# connector.net
KiCad netlist of a schematic drawn in Altium Designer
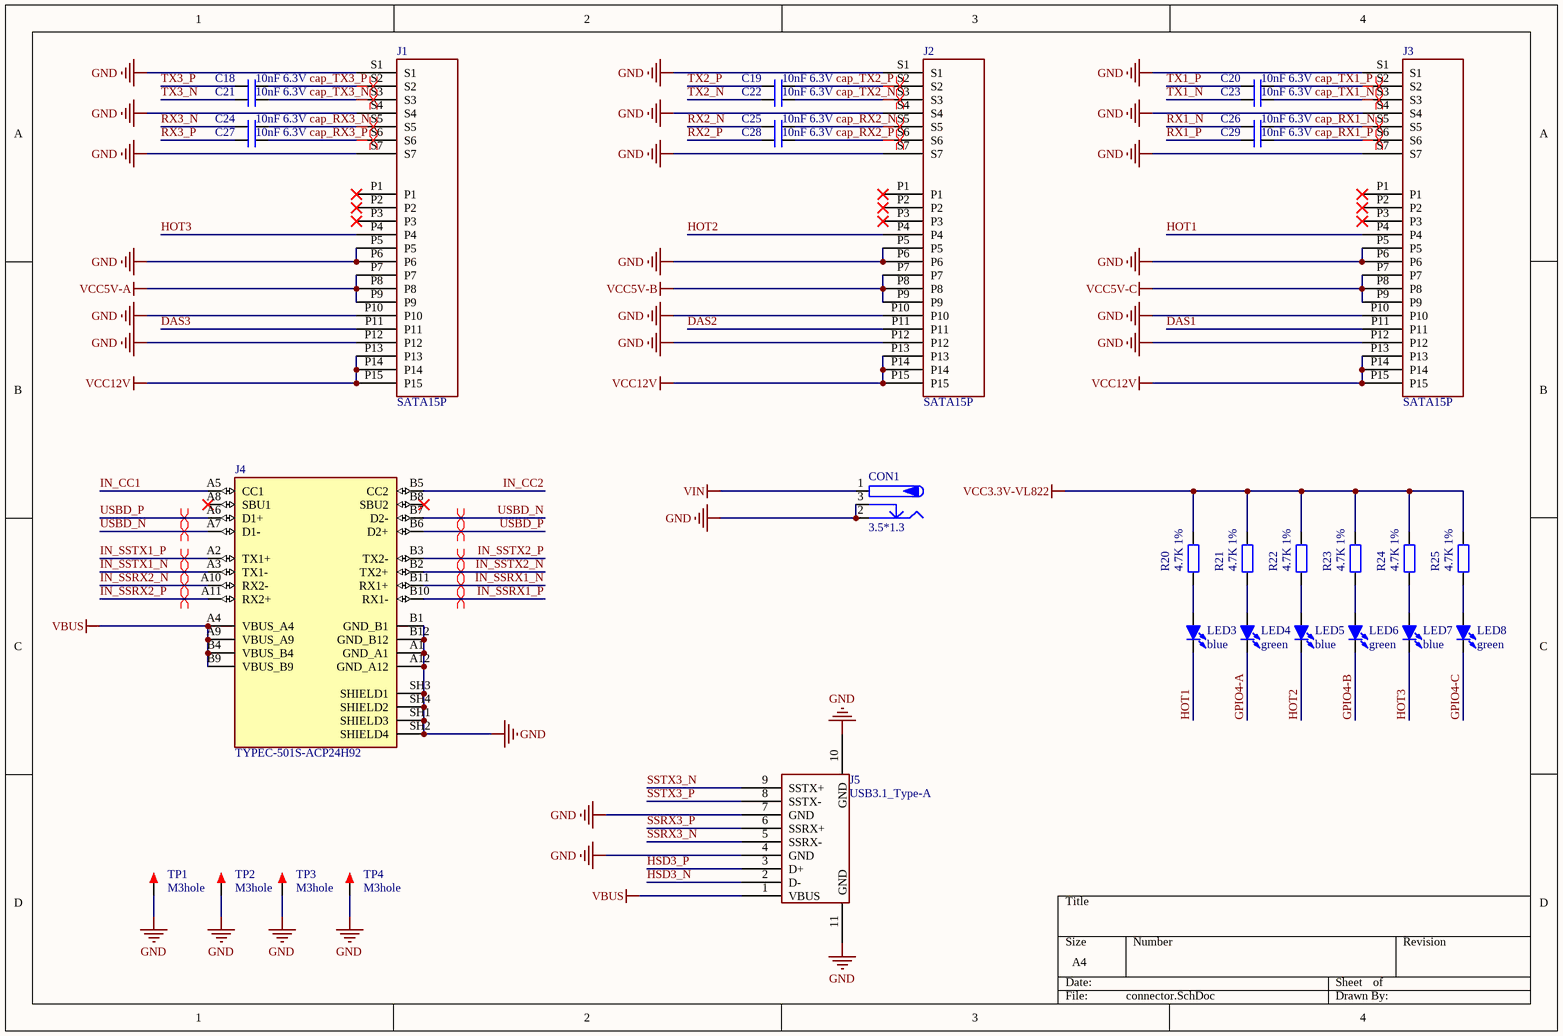
[diagram p0: connector.SchDoc]

(export (version "E")
  (design (tool "Eeschema 10.0.6"))
  (components
    (comp (ref "C18")
      (value "10nF 6.3V")
      (footprint "C0402_L")
      (description "无极性贴片电容")
      (fields (field (name "版权归属") "源创客"))
      (libsource (lib "Capacitor") (part "C"))
    )
    (comp (ref "C19")
      (value "10nF 6.3V")
      (footprint "C0402_L")
      (description "无极性贴片电容")
      (fields (field (name "版权归属") "源创客"))
      (libsource (lib "Capacitor") (part "C"))
    )
    (comp (ref "C20")
      (value "10nF 6.3V")
      (footprint "C0402_L")
      (description "无极性贴片电容")
      (fields (field (name "版权归属") "源创客"))
      (libsource (lib "Capacitor") (part "C"))
    )
    (comp (ref "C21")
      (value "10nF 6.3V")
      (footprint "C0402_L")
      (description "无极性贴片电容")
      (fields (field (name "版权归属") "源创客"))
      (libsource (lib "Capacitor") (part "C"))
    )
    (comp (ref "C22")
      (value "10nF 6.3V")
      (footprint "C0402_L")
      (description "无极性贴片电容")
      (fields (field (name "版权归属") "源创客"))
      (libsource (lib "Capacitor") (part "C"))
    )
    (comp (ref "C23")
      (value "10nF 6.3V")
      (footprint "C0402_L")
      (description "无极性贴片电容")
      (fields (field (name "版权归属") "源创客"))
      (libsource (lib "Capacitor") (part "C"))
    )
    (comp (ref "C24")
      (value "10nF 6.3V")
      (footprint "C0402_L")
      (description "无极性贴片电容")
      (fields (field (name "版权归属") "源创客"))
      (libsource (lib "Capacitor") (part "C"))
    )
    (comp (ref "C25")
      (value "10nF 6.3V")
      (footprint "C0402_L")
      (description "无极性贴片电容")
      (fields (field (name "版权归属") "源创客"))
      (libsource (lib "Capacitor") (part "C"))
    )
    (comp (ref "C26")
      (value "10nF 6.3V")
      (footprint "C0402_L")
      (description "无极性贴片电容")
      (fields (field (name "版权归属") "源创客"))
      (libsource (lib "Capacitor") (part "C"))
    )
    (comp (ref "C27")
      (value "10nF 6.3V")
      (footprint "C0402_L")
      (description "无极性贴片电容")
      (fields (field (name "版权归属") "源创客"))
      (libsource (lib "Capacitor") (part "C"))
    )
    (comp (ref "C28")
      (value "10nF 6.3V")
      (footprint "C0402_L")
      (description "无极性贴片电容")
      (fields (field (name "版权归属") "源创客"))
      (libsource (lib "Capacitor") (part "C"))
    )
    (comp (ref "C29")
      (value "10nF 6.3V")
      (footprint "C0402_L")
      (description "无极性贴片电容")
      (fields (field (name "版权归属") "源创客"))
      (libsource (lib "Capacitor") (part "C"))
    )
    (comp (ref "CON1")
      (value "3.5*1.3")
      (footprint "DC-012")
      (description "低压电源接口")
      (fields (field (name "版权归属") "源创客"))
      (libsource (lib "Connector-PWR") (part "P-DC"))
    )
    (comp (ref "J1")
      (value "SATA15P")
      (footprint "SATA 15P 贴片")
      (libsource (lib "Connector-SATA&SAS") (part "SATA15P"))
    )
    (comp (ref "J2")
      (value "SATA15P")
      (footprint "SATA 15P 贴片")
      (libsource (lib "Connector-SATA&SAS") (part "SATA15P"))
    )
    (comp (ref "J3")
      (value "SATA15P")
      (footprint "SATA 15P 贴片")
      (libsource (lib "Connector-SATA&SAS") (part "SATA15P"))
    )
    (comp (ref "J4")
      (value "TYPEC-501S-ACP24H92")
      (footprint "TypeC 24p 直立")
      (fields (field (name "MF") "Molex") (field (name "MP") "1054500101"))
      (libsource (lib "Connector-USB") (part "Typec 24p"))
    )
    (comp (ref "J5")
      (value "USB3.1_Type-A")
      (footprint "USB3.1_Type-A 立式直插")
      (description "USB接口")
      (libsource (lib "Connector-USB") (part "USB3.1_Type-A"))
    )
    (comp (ref "LED3")
      (value "blue")
      (footprint "LED 0805B")
      (description "插件LED")
      (fields (field (name "版权归属") "源创客"))
      (libsource (lib "LED") (part "LED-3MM"))
    )
    (comp (ref "LED4")
      (value "green")
      (footprint "LED 0805G")
      (description "插件LED")
      (fields (field (name "版权归属") "源创客"))
      (libsource (lib "LED") (part "LED-3MM"))
    )
    (comp (ref "LED5")
      (value "blue")
      (footprint "LED 0805B")
      (description "插件LED")
      (fields (field (name "版权归属") "源创客"))
      (libsource (lib "LED") (part "LED-3MM"))
    )
    (comp (ref "LED6")
      (value "green")
      (footprint "LED 0805G")
      (description "插件LED")
      (fields (field (name "版权归属") "源创客"))
      (libsource (lib "LED") (part "LED-3MM"))
    )
    (comp (ref "LED7")
      (value "blue")
      (footprint "LED 0805B")
      (description "插件LED")
      (fields (field (name "版权归属") "源创客"))
      (libsource (lib "LED") (part "LED-3MM"))
    )
    (comp (ref "LED8")
      (value "green")
      (footprint "LED 0805G")
      (description "插件LED")
      (fields (field (name "版权归属") "源创客"))
      (libsource (lib "LED") (part "LED-3MM"))
    )
    (comp (ref "R20")
      (value "4.7K 1%")
      (footprint "R0402_L")
      (description "贴片电阻")
      (fields (field (name "版权归属") "源创客"))
      (libsource (lib "Resistor") (part "R"))
    )
    (comp (ref "R21")
      (value "4.7K 1%")
      (footprint "R0402_L")
      (description "贴片电阻")
      (fields (field (name "版权归属") "源创客"))
      (libsource (lib "Resistor") (part "R"))
    )
    (comp (ref "R22")
      (value "4.7K 1%")
      (footprint "R0402_L")
      (description "贴片电阻")
      (fields (field (name "版权归属") "源创客"))
      (libsource (lib "Resistor") (part "R"))
    )
    (comp (ref "R23")
      (value "4.7K 1%")
      (footprint "R0402_L")
      (description "贴片电阻")
      (fields (field (name "版权归属") "源创客"))
      (libsource (lib "Resistor") (part "R"))
    )
    (comp (ref "R24")
      (value "4.7K 1%")
      (footprint "R0402_L")
      (description "贴片电阻")
      (fields (field (name "版权归属") "源创客"))
      (libsource (lib "Resistor") (part "R"))
    )
    (comp (ref "R25")
      (value "4.7K 1%")
      (footprint "R0402_L")
      (description "贴片电阻")
      (fields (field (name "版权归属") "源创客"))
      (libsource (lib "Resistor") (part "R"))
    )
    (comp (ref "TP1")
      (value "M3hole")
      (footprint "m3内嵌螺母贴片")
      (description "测试点")
      (fields (field (name "版权归属") "源创客"))
      (libsource (lib "Hole") (part "TEST"))
    )
    (comp (ref "TP2")
      (value "M3hole")
      (footprint "m3内嵌螺母贴片")
      (description "测试点")
      (fields (field (name "版权归属") "源创客"))
      (libsource (lib "Hole") (part "TEST"))
    )
    (comp (ref "TP3")
      (value "M3hole")
      (footprint "m3内嵌螺母贴片")
      (description "测试点")
      (fields (field (name "版权归属") "源创客"))
      (libsource (lib "Hole") (part "TEST"))
    )
    (comp (ref "TP4")
      (value "M3hole")
      (footprint "m3内嵌螺母贴片")
      (description "测试点")
      (fields (field (name "版权归属") "源创客"))
      (libsource (lib "Hole") (part "TEST"))
    )
  )
  (nets
    (net (code "1") (name "/DAS1") (class "Default")
      (node (ref "J3") (pin "P11") (pinfunction "P11_P11") (pintype "passive"))
    )
    (net (code "2") (name "/DAS2") (class "Default")
      (node (ref "J2") (pin "P11") (pinfunction "P11_P11") (pintype "passive"))
    )
    (net (code "3") (name "/DAS3") (class "Default")
      (node (ref "J1") (pin "P11") (pinfunction "P11_P11") (pintype "passive"))
    )
    (net (code "4") (name "/GPIO4-A") (class "Default")
      (node (ref "LED4") (pin "2") (pinfunction "K_2") (pintype "passive"))
    )
    (net (code "5") (name "/GPIO4-B") (class "Default")
      (node (ref "LED6") (pin "2") (pinfunction "K_2") (pintype "passive"))
    )
    (net (code "6") (name "/GPIO4-C") (class "Default")
      (node (ref "LED8") (pin "2") (pinfunction "K_2") (pintype "passive"))
    )
    (net (code "7") (name "/HOT1") (class "Default")
      (node (ref "J3") (pin "P4") (pinfunction "P4_P4") (pintype "passive"))
      (node (ref "LED3") (pin "2") (pinfunction "K_2") (pintype "passive"))
    )
    (net (code "8") (name "/HOT2") (class "Default")
      (node (ref "J2") (pin "P4") (pinfunction "P4_P4") (pintype "passive"))
      (node (ref "LED5") (pin "2") (pinfunction "K_2") (pintype "passive"))
    )
    (net (code "9") (name "/HOT3") (class "Default")
      (node (ref "J1") (pin "P4") (pinfunction "P4_P4") (pintype "passive"))
      (node (ref "LED7") (pin "2") (pinfunction "K_2") (pintype "passive"))
    )
    (net (code "10") (name "/HSD3_N") (class "Default")
      (node (ref "J5") (pin "2") (pinfunction "D-_2") (pintype "passive"))
    )
    (net (code "11") (name "/HSD3_P") (class "Default")
      (node (ref "J5") (pin "3") (pinfunction "D+_3") (pintype "passive"))
    )
    (net (code "12") (name "/IN_CC1") (class "Default")
      (node (ref "J4") (pin "A5") (pinfunction "CC1_A5") (pintype "bidirectional"))
    )
    (net (code "13") (name "/IN_CC2") (class "Default")
      (node (ref "J4") (pin "B5") (pinfunction "CC2_B5") (pintype "bidirectional"))
    )
    (net (code "14") (name "/IN_SSRX1_N") (class "Default")
      (node (ref "J4") (pin "B11") (pinfunction "RX1+_B11") (pintype "bidirectional"))
    )
    (net (code "15") (name "/IN_SSRX1_P") (class "Default")
      (node (ref "J4") (pin "B10") (pinfunction "RX1-_B10") (pintype "bidirectional"))
    )
    (net (code "16") (name "/IN_SSRX2_N") (class "Default")
      (node (ref "J4") (pin "A10") (pinfunction "RX2-_A10") (pintype "bidirectional"))
    )
    (net (code "17") (name "/IN_SSRX2_P") (class "Default")
      (node (ref "J4") (pin "A11") (pinfunction "RX2+_A11") (pintype "bidirectional"))
    )
    (net (code "18") (name "/IN_SSTX1_N") (class "Default")
      (node (ref "J4") (pin "A3") (pinfunction "TX1-_A3") (pintype "bidirectional"))
    )
    (net (code "19") (name "/IN_SSTX1_P") (class "Default")
      (node (ref "J4") (pin "A2") (pinfunction "TX1+_A2") (pintype "bidirectional"))
    )
    (net (code "20") (name "/IN_SSTX2_N") (class "Default")
      (node (ref "J4") (pin "B2") (pinfunction "TX2+_B2") (pintype "bidirectional"))
    )
    (net (code "21") (name "/IN_SSTX2_P") (class "Default")
      (node (ref "J4") (pin "B3") (pinfunction "TX2-_B3") (pintype "bidirectional"))
    )
    (net (code "22") (name "/RX1_N") (class "Default")
      (node (ref "C26") (pin "2") (pinfunction "2_2") (pintype "passive"))
    )
    (net (code "23") (name "/RX1_P") (class "Default")
      (node (ref "C29") (pin "2") (pinfunction "2_2") (pintype "passive"))
    )
    (net (code "24") (name "/RX2_N") (class "Default")
      (node (ref "C25") (pin "2") (pinfunction "2_2") (pintype "passive"))
    )
    (net (code "25") (name "/RX2_P") (class "Default")
      (node (ref "C28") (pin "2") (pinfunction "2_2") (pintype "passive"))
    )
    (net (code "26") (name "/RX3_N") (class "Default")
      (node (ref "C24") (pin "2") (pinfunction "2_2") (pintype "passive"))
    )
    (net (code "27") (name "/RX3_P") (class "Default")
      (node (ref "C27") (pin "2") (pinfunction "2_2") (pintype "passive"))
    )
    (net (code "28") (name "/SSRX3_N") (class "Default")
      (node (ref "J5") (pin "5") (pinfunction "SSRX-_5") (pintype "passive"))
    )
    (net (code "29") (name "/SSRX3_P") (class "Default")
      (node (ref "J5") (pin "6") (pinfunction "SSRX+_6") (pintype "passive"))
    )
    (net (code "30") (name "/SSTX3_N") (class "Default")
      (node (ref "J5") (pin "9") (pinfunction "SSTX+_9") (pintype "passive"))
    )
    (net (code "31") (name "/SSTX3_P") (class "Default")
      (node (ref "J5") (pin "8") (pinfunction "SSTX-_8") (pintype "passive"))
    )
    (net (code "32") (name "/TX1_N") (class "Default")
      (node (ref "C23") (pin "2") (pinfunction "2_2") (pintype "passive"))
    )
    (net (code "33") (name "/TX1_P") (class "Default")
      (node (ref "C20") (pin "2") (pinfunction "2_2") (pintype "passive"))
    )
    (net (code "34") (name "/TX2_N") (class "Default")
      (node (ref "C22") (pin "2") (pinfunction "2_2") (pintype "passive"))
    )
    (net (code "35") (name "/TX2_P") (class "Default")
      (node (ref "C19") (pin "2") (pinfunction "2_2") (pintype "passive"))
    )
    (net (code "36") (name "/TX3_N") (class "Default")
      (node (ref "C21") (pin "2") (pinfunction "2_2") (pintype "passive"))
    )
    (net (code "37") (name "/TX3_P") (class "Default")
      (node (ref "C18") (pin "2") (pinfunction "2_2") (pintype "passive"))
    )
    (net (code "38") (name "/USBD_N") (class "Default")
      (node (ref "J4") (pin "A7") (pinfunction "D1-_A7") (pintype "bidirectional"))
      (node (ref "J4") (pin "B7") (pinfunction "D2-_B7") (pintype "bidirectional"))
    )
    (net (code "39") (name "/USBD_P") (class "Default")
      (node (ref "J4") (pin "A6") (pinfunction "D1+_A6") (pintype "bidirectional"))
      (node (ref "J4") (pin "B6") (pinfunction "D2+_B6") (pintype "bidirectional"))
    )
    (net (code "40") (name "/cap_RX1_N") (class "Default")
      (node (ref "C26") (pin "1") (pinfunction "1_1") (pintype "passive"))
      (node (ref "J3") (pin "S5") (pinfunction "S5_S5") (pintype "passive"))
    )
    (net (code "41") (name "/cap_RX1_P") (class "Default")
      (node (ref "C29") (pin "1") (pinfunction "1_1") (pintype "passive"))
      (node (ref "J3") (pin "S6") (pinfunction "S6_S6") (pintype "passive"))
    )
    (net (code "42") (name "/cap_RX2_N") (class "Default")
      (node (ref "C25") (pin "1") (pinfunction "1_1") (pintype "passive"))
      (node (ref "J2") (pin "S5") (pinfunction "S5_S5") (pintype "passive"))
    )
    (net (code "43") (name "/cap_RX2_P") (class "Default")
      (node (ref "C28") (pin "1") (pinfunction "1_1") (pintype "passive"))
      (node (ref "J2") (pin "S6") (pinfunction "S6_S6") (pintype "passive"))
    )
    (net (code "44") (name "/cap_RX3_N") (class "Default")
      (node (ref "C24") (pin "1") (pinfunction "1_1") (pintype "passive"))
      (node (ref "J1") (pin "S5") (pinfunction "S5_S5") (pintype "passive"))
    )
    (net (code "45") (name "/cap_RX3_P") (class "Default")
      (node (ref "C27") (pin "1") (pinfunction "1_1") (pintype "passive"))
      (node (ref "J1") (pin "S6") (pinfunction "S6_S6") (pintype "passive"))
    )
    (net (code "46") (name "/cap_TX1_N") (class "Default")
      (node (ref "C23") (pin "1") (pinfunction "1_1") (pintype "passive"))
      (node (ref "J3") (pin "S3") (pinfunction "S3_S3") (pintype "passive"))
    )
    (net (code "47") (name "/cap_TX1_P") (class "Default")
      (node (ref "C20") (pin "1") (pinfunction "1_1") (pintype "passive"))
      (node (ref "J3") (pin "S2") (pinfunction "S2_S2") (pintype "passive"))
    )
    (net (code "48") (name "/cap_TX2_N") (class "Default")
      (node (ref "C22") (pin "1") (pinfunction "1_1") (pintype "passive"))
      (node (ref "J2") (pin "S3") (pinfunction "S3_S3") (pintype "passive"))
    )
    (net (code "49") (name "/cap_TX2_P") (class "Default")
      (node (ref "C19") (pin "1") (pinfunction "1_1") (pintype "passive"))
      (node (ref "J2") (pin "S2") (pinfunction "S2_S2") (pintype "passive"))
    )
    (net (code "50") (name "/cap_TX3_N") (class "Default")
      (node (ref "C21") (pin "1") (pinfunction "1_1") (pintype "passive"))
      (node (ref "J1") (pin "S3") (pinfunction "S3_S3") (pintype "passive"))
    )
    (net (code "51") (name "/cap_TX3_P") (class "Default")
      (node (ref "C18") (pin "1") (pinfunction "1_1") (pintype "passive"))
      (node (ref "J1") (pin "S2") (pinfunction "S2_S2") (pintype "passive"))
    )
    (net (code "52") (name "GND") (class "Default")
      (node (ref "CON1") (pin "2") (pintype "power_in"))
      (node (ref "CON1") (pin "3") (pintype "power_in"))
      (node (ref "J1") (pin "P10") (pinfunction "P10_P10") (pintype "passive"))
      (node (ref "J1") (pin "P12") (pinfunction "P12_P12") (pintype "passive"))
      (node (ref "J1") (pin "P5") (pinfunction "P5_P5") (pintype "passive"))
      (node (ref "J1") (pin "P6") (pinfunction "P6_P6") (pintype "passive"))
      (node (ref "J1") (pin "S1") (pinfunction "S1_S1") (pintype "passive"))
      (node (ref "J1") (pin "S4") (pinfunction "S4_S4") (pintype "passive"))
      (node (ref "J1") (pin "S7") (pinfunction "S7_S7") (pintype "passive"))
      (node (ref "J2") (pin "P10") (pinfunction "P10_P10") (pintype "passive"))
      (node (ref "J2") (pin "P12") (pinfunction "P12_P12") (pintype "passive"))
      (node (ref "J2") (pin "P5") (pinfunction "P5_P5") (pintype "passive"))
      (node (ref "J2") (pin "P6") (pinfunction "P6_P6") (pintype "passive"))
      (node (ref "J2") (pin "S1") (pinfunction "S1_S1") (pintype "passive"))
      (node (ref "J2") (pin "S4") (pinfunction "S4_S4") (pintype "passive"))
      (node (ref "J2") (pin "S7") (pinfunction "S7_S7") (pintype "passive"))
      (node (ref "J3") (pin "P10") (pinfunction "P10_P10") (pintype "passive"))
      (node (ref "J3") (pin "P12") (pinfunction "P12_P12") (pintype "passive"))
      (node (ref "J3") (pin "P5") (pinfunction "P5_P5") (pintype "passive"))
      (node (ref "J3") (pin "P6") (pinfunction "P6_P6") (pintype "passive"))
      (node (ref "J3") (pin "S1") (pinfunction "S1_S1") (pintype "passive"))
      (node (ref "J3") (pin "S4") (pinfunction "S4_S4") (pintype "passive"))
      (node (ref "J3") (pin "S7") (pinfunction "S7_S7") (pintype "passive"))
      (node (ref "J4") (pin "A1") (pinfunction "GND_A1_A1") (pintype "power_in"))
      (node (ref "J4") (pin "A12") (pinfunction "GND_A12_A12") (pintype "power_in"))
      (node (ref "J4") (pin "B1") (pinfunction "GND_B1_B1") (pintype "power_in"))
      (node (ref "J4") (pin "B12") (pinfunction "GND_B12_B12") (pintype "power_in"))
      (node (ref "J4") (pin "SH1") (pinfunction "SHIELD3_SH1") (pintype "passive"))
      (node (ref "J4") (pin "SH2") (pinfunction "SHIELD4_SH2") (pintype "passive"))
      (node (ref "J4") (pin "SH3") (pinfunction "SHIELD1_SH3") (pintype "passive"))
      (node (ref "J4") (pin "SH4") (pinfunction "SHIELD2_SH4") (pintype "passive"))
      (node (ref "J5") (pin "10") (pinfunction "GND_10") (pintype "passive"))
      (node (ref "J5") (pin "11") (pinfunction "GND_11") (pintype "passive"))
      (node (ref "J5") (pin "4") (pinfunction "GND_4") (pintype "passive"))
      (node (ref "J5") (pin "7") (pinfunction "GND_7") (pintype "passive"))
      (node (ref "TP1") (pin "1") (pinfunction "1_1") (pintype "passive"))
      (node (ref "TP2") (pin "1") (pinfunction "1_1") (pintype "passive"))
      (node (ref "TP3") (pin "1") (pinfunction "1_1") (pintype "passive"))
      (node (ref "TP4") (pin "1") (pinfunction "1_1") (pintype "passive"))
    )
    (net (code "53") (name "Net-(LED3-A)") (class "Default")
      (node (ref "LED3") (pin "1") (pinfunction "A_1") (pintype "passive"))
      (node (ref "R20") (pin "2") (pinfunction "2_2") (pintype "passive"))
    )
    (net (code "54") (name "Net-(LED4-A)") (class "Default")
      (node (ref "LED4") (pin "1") (pinfunction "A_1") (pintype "passive"))
      (node (ref "R21") (pin "2") (pinfunction "2_2") (pintype "passive"))
    )
    (net (code "55") (name "Net-(LED5-A)") (class "Default")
      (node (ref "LED5") (pin "1") (pinfunction "A_1") (pintype "passive"))
      (node (ref "R22") (pin "2") (pinfunction "2_2") (pintype "passive"))
    )
    (net (code "56") (name "Net-(LED6-A)") (class "Default")
      (node (ref "LED6") (pin "1") (pinfunction "A_1") (pintype "passive"))
      (node (ref "R23") (pin "2") (pinfunction "2_2") (pintype "passive"))
    )
    (net (code "57") (name "Net-(LED7-A)") (class "Default")
      (node (ref "LED7") (pin "1") (pinfunction "A_1") (pintype "passive"))
      (node (ref "R24") (pin "2") (pinfunction "2_2") (pintype "passive"))
    )
    (net (code "58") (name "Net-(LED8-A)") (class "Default")
      (node (ref "LED8") (pin "1") (pinfunction "A_1") (pintype "passive"))
      (node (ref "R25") (pin "2") (pinfunction "2_2") (pintype "passive"))
    )
    (net (code "59") (name "VBUS") (class "Default")
      (node (ref "J4") (pin "A4") (pinfunction "VBUS_A4_A4") (pintype "power_in"))
      (node (ref "J4") (pin "A9") (pinfunction "VBUS_A9_A9") (pintype "power_in"))
      (node (ref "J4") (pin "B4") (pinfunction "VBUS_B4_B4") (pintype "power_in"))
      (node (ref "J4") (pin "B9") (pinfunction "VBUS_B9_B9") (pintype "power_in"))
      (node (ref "J5") (pin "1") (pinfunction "VBUS_1") (pintype "passive"))
    )
    (net (code "60") (name "VCC3.3V-VL822") (class "Default")
      (node (ref "R20") (pin "1") (pinfunction "1_1") (pintype "passive"))
      (node (ref "R21") (pin "1") (pinfunction "1_1") (pintype "passive"))
      (node (ref "R22") (pin "1") (pinfunction "1_1") (pintype "passive"))
      (node (ref "R23") (pin "1") (pinfunction "1_1") (pintype "passive"))
      (node (ref "R24") (pin "1") (pinfunction "1_1") (pintype "passive"))
      (node (ref "R25") (pin "1") (pinfunction "1_1") (pintype "passive"))
    )
    (net (code "61") (name "VCC5V-A") (class "Default")
      (node (ref "J1") (pin "P7") (pinfunction "P7_P7") (pintype "passive"))
      (node (ref "J1") (pin "P8") (pinfunction "P8_P8") (pintype "passive"))
      (node (ref "J1") (pin "P9") (pinfunction "P9_P9") (pintype "passive"))
    )
    (net (code "62") (name "VCC5V-B") (class "Default")
      (node (ref "J2") (pin "P7") (pinfunction "P7_P7") (pintype "passive"))
      (node (ref "J2") (pin "P8") (pinfunction "P8_P8") (pintype "passive"))
      (node (ref "J2") (pin "P9") (pinfunction "P9_P9") (pintype "passive"))
    )
    (net (code "63") (name "VCC5V-C") (class "Default")
      (node (ref "J3") (pin "P7") (pinfunction "P7_P7") (pintype "passive"))
      (node (ref "J3") (pin "P8") (pinfunction "P8_P8") (pintype "passive"))
      (node (ref "J3") (pin "P9") (pinfunction "P9_P9") (pintype "passive"))
    )
    (net (code "64") (name "VCC12V") (class "Default")
      (node (ref "J1") (pin "P13") (pinfunction "P13_P13") (pintype "passive"))
      (node (ref "J1") (pin "P14") (pinfunction "P14_P14") (pintype "passive"))
      (node (ref "J1") (pin "P15") (pinfunction "P15_P15") (pintype "passive"))
      (node (ref "J2") (pin "P13") (pinfunction "P13_P13") (pintype "passive"))
      (node (ref "J2") (pin "P14") (pinfunction "P14_P14") (pintype "passive"))
      (node (ref "J2") (pin "P15") (pinfunction "P15_P15") (pintype "passive"))
      (node (ref "J3") (pin "P13") (pinfunction "P13_P13") (pintype "passive"))
      (node (ref "J3") (pin "P14") (pinfunction "P14_P14") (pintype "passive"))
      (node (ref "J3") (pin "P15") (pinfunction "P15_P15") (pintype "passive"))
    )
    (net (code "65") (name "VIN") (class "Default") (node (ref "CON1") (pin "1") (pintype "power_in")))
    (net (code "66") (name "unconnected-(J1-PadP1)") (class "Default")
      (node (ref "J1") (pin "P1") (pinfunction "P1_P1") (pintype "passive+no_connect"))
    )
    (net (code "67") (name "unconnected-(J1-PadP2)") (class "Default")
      (node (ref "J1") (pin "P2") (pinfunction "P2_P2") (pintype "passive+no_connect"))
    )
    (net (code "68") (name "unconnected-(J1-PadP3)") (class "Default")
      (node (ref "J1") (pin "P3") (pinfunction "P3_P3") (pintype "passive+no_connect"))
    )
    (net (code "69") (name "unconnected-(J2-PadP1)") (class "Default")
      (node (ref "J2") (pin "P1") (pinfunction "P1_P1") (pintype "passive+no_connect"))
    )
    (net (code "70") (name "unconnected-(J2-PadP2)") (class "Default")
      (node (ref "J2") (pin "P2") (pinfunction "P2_P2") (pintype "passive+no_connect"))
    )
    (net (code "71") (name "unconnected-(J2-PadP3)") (class "Default")
      (node (ref "J2") (pin "P3") (pinfunction "P3_P3") (pintype "passive+no_connect"))
    )
    (net (code "72") (name "unconnected-(J3-PadP1)") (class "Default")
      (node (ref "J3") (pin "P1") (pinfunction "P1_P1") (pintype "passive+no_connect"))
    )
    (net (code "73") (name "unconnected-(J3-PadP2)") (class "Default")
      (node (ref "J3") (pin "P2") (pinfunction "P2_P2") (pintype "passive+no_connect"))
    )
    (net (code "74") (name "unconnected-(J3-PadP3)") (class "Default")
      (node (ref "J3") (pin "P3") (pinfunction "P3_P3") (pintype "passive+no_connect"))
    )
    (net (code "75") (name "unconnected-(J4-SBU1-PadA8)") (class "Default")
      (node (ref "J4") (pin "A8") (pinfunction "SBU1_A8") (pintype "bidirectional+no_connect"))
    )
    (net (code "76") (name "unconnected-(J4-SBU2-PadB8)") (class "Default")
      (node (ref "J4") (pin "B8") (pinfunction "SBU2_B8") (pintype "bidirectional+no_connect"))
    )
  )
)
